# layout-tutorial.net
KiCad netlist of a schematic drawn in EAGLE
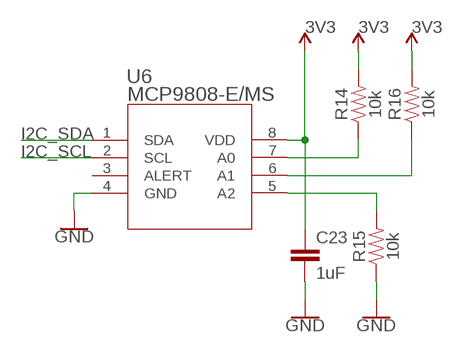
[diagram p0: schematic, sheet 1]

(export (version "E")
  (design (tool "Eeschema 10.0.6"))
  (components
    (comp (ref "C23")
      (value "1uF")
      (footprint "eagle-import:0603@1")
      (libsource (lib "eagle-import") (part "0.1UF-0603-100V-10%"))
    )
    (comp (ref "R14")
      (value "10k")
      (footprint "eagle-import:0603")
      (libsource (lib "eagle-import") (part "10KOHM-0603-1/10W-1%"))
    )
    (comp (ref "R15")
      (value "10k")
      (footprint "eagle-import:0603")
      (libsource (lib "eagle-import") (part "10KOHM-0603-1/10W-1%"))
    )
    (comp (ref "R16")
      (value "10k")
      (footprint "eagle-import:0603")
      (libsource (lib "eagle-import") (part "10KOHM-0603-1/10W-1%"))
    )
    (comp (ref "U6")
      (value "MCP9808-E/MS")
      (footprint "eagle-import:MSOP8_MC")
      (libsource (lib "eagle-import") (part "MCP9808-E/MS"))
    )
  )
  (nets
    (net (code "1") (name "/I2C_SCL") (class "Default")
      (node (ref "U6") (pin "2") (pinfunction "SCL_2") (pintype "passive"))
    )
    (net (code "2") (name "/I2C_SDA") (class "Default")
      (node (ref "U6") (pin "1") (pinfunction "SDA_1") (pintype "passive"))
    )
    (net (code "3") (name "3.3V") (class "Default")
      (node (ref "C23") (pin "1") (pinfunction "1_1") (pintype "passive"))
      (node (ref "R14") (pin "2") (pinfunction "2_2") (pintype "passive"))
      (node (ref "R16") (pin "2") (pinfunction "2_2") (pintype "passive"))
      (node (ref "U6") (pin "8") (pinfunction "VDD_8") (pintype "power_in"))
    )
    (net (code "4") (name "GND") (class "Default")
      (node (ref "C23") (pin "2") (pinfunction "2_2") (pintype "passive"))
      (node (ref "R15") (pin "1") (pinfunction "1_1") (pintype "passive"))
      (node (ref "U6") (pin "4") (pinfunction "GND_4") (pintype "power_in"))
    )
    (net (code "5") (name "Net-(U6-A0)") (class "Default")
      (node (ref "R14") (pin "1") (pinfunction "1_1") (pintype "passive"))
      (node (ref "U6") (pin "7") (pinfunction "A0_7") (pintype "passive"))
    )
    (net (code "6") (name "Net-(U6-A1)") (class "Default")
      (node (ref "R16") (pin "1") (pinfunction "1_1") (pintype "passive"))
      (node (ref "U6") (pin "6") (pinfunction "A1_6") (pintype "passive"))
    )
    (net (code "7") (name "Net-(U6-A2)") (class "Default")
      (node (ref "R15") (pin "2") (pinfunction "2_2") (pintype "passive"))
      (node (ref "U6") (pin "5") (pinfunction "A2_5") (pintype "passive"))
    )
    (net (code "8") (name "unconnected-(U6-ALERT-Pad3)") (class "Default")
      (node (ref "U6") (pin "3") (pinfunction "ALERT_3") (pintype "output"))
    )
  )
)
